# Lightpack5_5.net
KiCad netlist of a schematic drawn in EAGLE
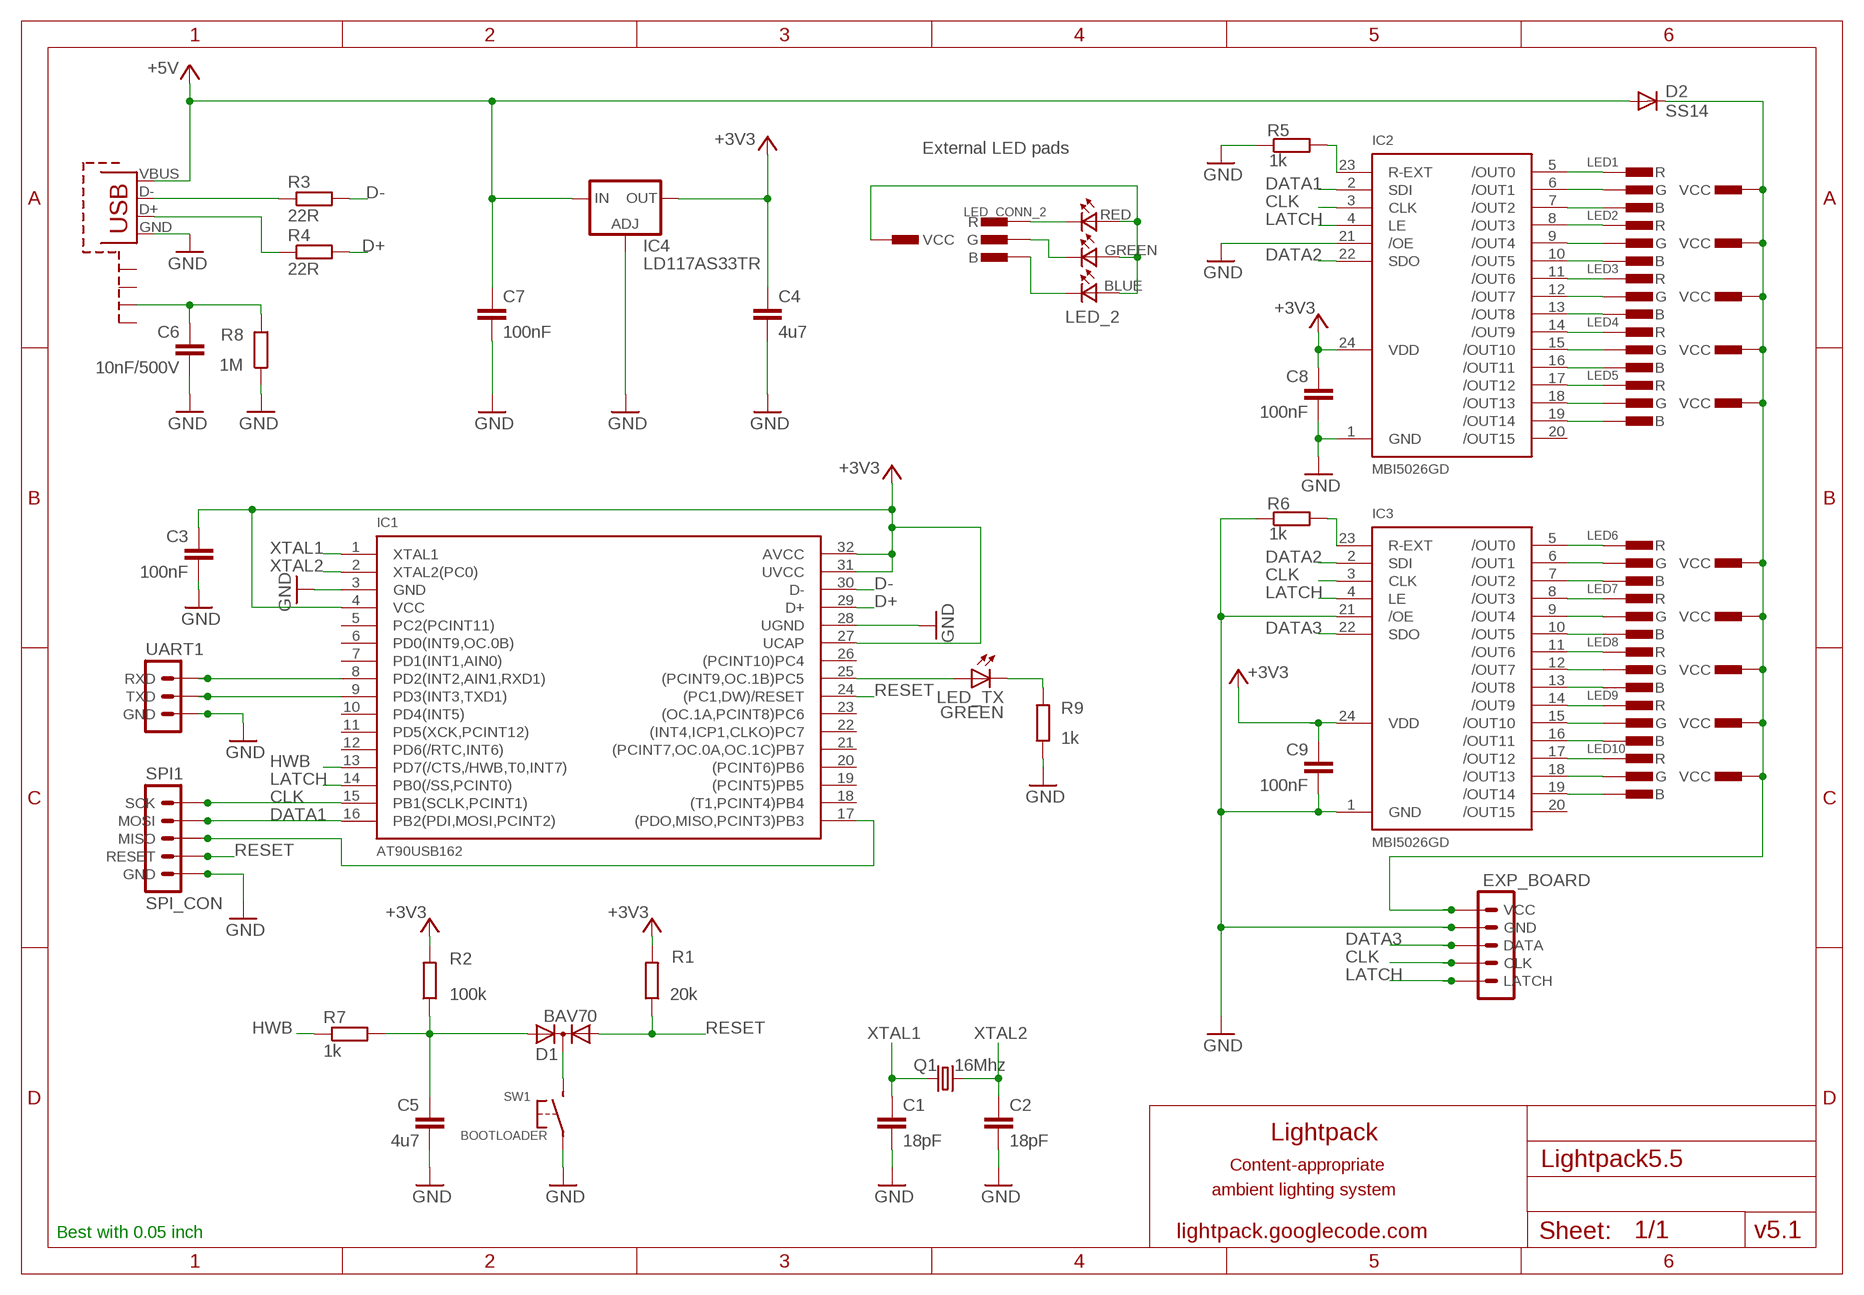
[diagram p0: schematic, sheet 1]

(export (version "E")
  (design (tool "Eeschema 10.0.6"))
  (components
    (comp (ref "C1")
      (value "18pF")
      (footprint "eagle-import:C1206")
      (libsource (lib "eagle-import") (part "C-EUC1206"))
    )
    (comp (ref "C2")
      (value "18pF")
      (footprint "eagle-import:C1206")
      (libsource (lib "eagle-import") (part "C-EUC1206"))
    )
    (comp (ref "C3")
      (value "100nF")
      (footprint "eagle-import:C1206")
      (libsource (lib "eagle-import") (part "C-EUC1206"))
    )
    (comp (ref "C4")
      (value "4u7")
      (footprint "eagle-import:C1206")
      (libsource (lib "eagle-import") (part "C-EUC1206"))
    )
    (comp (ref "C5")
      (value "4u7")
      (footprint "eagle-import:C1206")
      (libsource (lib "eagle-import") (part "C-EUC1206"))
    )
    (comp (ref "C6")
      (value "10nF/500V")
      (footprint "eagle-import:C1206")
      (libsource (lib "eagle-import") (part "C-EUC1206"))
    )
    (comp (ref "C7")
      (value "100nF")
      (footprint "eagle-import:C1206")
      (libsource (lib "eagle-import") (part "C-EUC1206"))
    )
    (comp (ref "C8")
      (value "100nF")
      (footprint "eagle-import:C1206")
      (libsource (lib "eagle-import") (part "C-EUC1206"))
    )
    (comp (ref "C9")
      (value "100nF")
      (footprint "eagle-import:C1206")
      (libsource (lib "eagle-import") (part "C-EUC1206"))
    )
    (comp (ref "D1")
      (value "BAV70")
      (footprint "eagle-import:SOT23")
      (libsource (lib "eagle-import") (part "DIODE-2AC|CASOT23"))
    )
    (comp (ref "D2")
      (value "SS14")
      (footprint "eagle-import:SMB")
      (libsource (lib "eagle-import") (part "DIODE-SMB"))
    )
    (comp (ref "EXP_BOARD")
      (value "MA05-1")
      (footprint "eagle-import:MA05-1")
      (libsource (lib "eagle-import") (part "MA05-1"))
    )
    (comp (ref "IC1")
      (value "AT90USB162")
      (footprint "eagle-import:TQFP32")
      (libsource (lib "eagle-import") (part "AT90USB162"))
    )
    (comp (ref "IC2")
      (value "MBI5026GD")
      (footprint "eagle-import:SOP24-300-1.27")
      (libsource (lib "eagle-import") (part "MBI5026GD"))
    )
    (comp (ref "IC3")
      (value "MBI5026GD")
      (footprint "eagle-import:SOP24-300-1.27")
      (libsource (lib "eagle-import") (part "MBI5026GD"))
    )
    (comp (ref "IC4")
      (value "LD117AS33TR")
      (footprint "eagle-import:SOT223")
      (libsource (lib "eagle-import") (part "LD117A?S33TR"))
    )
    (comp (ref "LED1")
      (value "CON-RGB-LED")
      (footprint "eagle-import:CON-RGB-LED-TH")
      (libsource (lib "eagle-import") (part "CON-RGB-LED-TH"))
    )
    (comp (ref "LED2")
      (value "CON-RGB-LED")
      (footprint "eagle-import:CON-RGB-LED-TH")
      (libsource (lib "eagle-import") (part "CON-RGB-LED-TH"))
    )
    (comp (ref "LED3")
      (value "CON-RGB-LED")
      (footprint "eagle-import:CON-RGB-LED-TH")
      (libsource (lib "eagle-import") (part "CON-RGB-LED-TH"))
    )
    (comp (ref "LED4")
      (value "CON-RGB-LED")
      (footprint "eagle-import:CON-RGB-LED-TH")
      (libsource (lib "eagle-import") (part "CON-RGB-LED-TH"))
    )
    (comp (ref "LED5")
      (value "CON-RGB-LED")
      (footprint "eagle-import:CON-RGB-LED-TH")
      (libsource (lib "eagle-import") (part "CON-RGB-LED-TH"))
    )
    (comp (ref "LED6")
      (value "CON-RGB-LED")
      (footprint "eagle-import:CON-RGB-LED-TH")
      (libsource (lib "eagle-import") (part "CON-RGB-LED-TH"))
    )
    (comp (ref "LED7")
      (value "CON-RGB-LED")
      (footprint "eagle-import:CON-RGB-LED-TH")
      (libsource (lib "eagle-import") (part "CON-RGB-LED-TH"))
    )
    (comp (ref "LED8")
      (value "CON-RGB-LED")
      (footprint "eagle-import:CON-RGB-LED-TH")
      (libsource (lib "eagle-import") (part "CON-RGB-LED-TH"))
    )
    (comp (ref "LED9")
      (value "CON-RGB-LED")
      (footprint "eagle-import:CON-RGB-LED-TH")
      (libsource (lib "eagle-import") (part "CON-RGB-LED-TH"))
    )
    (comp (ref "LED10")
      (value "CON-RGB-LED")
      (footprint "eagle-import:CON-RGB-LED-TH")
      (libsource (lib "eagle-import") (part "CON-RGB-LED-TH"))
    )
    (comp (ref "LED_2")
      (value "TOPLED-3RF-W2SA50TS")
      (footprint "eagle-import:LP2C63-ST-RGB-SR0")
      (libsource (lib "eagle-import") (part "TOPLED-3RF-W2SA50TS"))
    )
    (comp (ref "LED_CONN_2")
      (value "CON-RGB-LED")
      (footprint "eagle-import:CON-RGB-LED-TH-EXT")
      (libsource (lib "eagle-import") (part "CON-RGB-LED-EXT"))
    )
    (comp (ref "LED_TX")
      (value "GREEN")
      (footprint "eagle-import:CHIPLED_0805")
      (libsource (lib "eagle-import") (part "LEDCHIPLED_0805"))
    )
    (comp (ref "Q1")
      (value "16Mhz")
      (footprint "eagle-import:HC49UP")
      (libsource (lib "eagle-import") (part "CRYSTALHC49UP"))
    )
    (comp (ref "R1")
      (value "20k")
      (footprint "eagle-import:R1206")
      (libsource (lib "eagle-import") (part "R-EU_R1206"))
    )
    (comp (ref "R2")
      (value "100k")
      (footprint "eagle-import:R1206")
      (libsource (lib "eagle-import") (part "R-EU_R1206_2"))
    )
    (comp (ref "R3")
      (value "22R")
      (footprint "eagle-import:R1206")
      (libsource (lib "eagle-import") (part "rcl_R-EU_R1206"))
    )
    (comp (ref "R4")
      (value "22R")
      (footprint "eagle-import:R1206")
      (libsource (lib "eagle-import") (part "rcl_R-EU_R1206"))
    )
    (comp (ref "R5")
      (value "1k")
      (footprint "eagle-import:R1206")
      (libsource (lib "eagle-import") (part "R-EU_R1206"))
    )
    (comp (ref "R6")
      (value "1k")
      (footprint "eagle-import:R1206")
      (libsource (lib "eagle-import") (part "R-EU_R1206"))
    )
    (comp (ref "R7")
      (value "1k")
      (footprint "eagle-import:R1206")
      (libsource (lib "eagle-import") (part "rcl_R-EU_R1206"))
    )
    (comp (ref "R8")
      (value "1M")
      (footprint "eagle-import:R1206")
      (libsource (lib "eagle-import") (part "rcl_R-EU_R1206"))
    )
    (comp (ref "R9")
      (value "1k")
      (footprint "eagle-import:R1206")
      (libsource (lib "eagle-import") (part "rcl_R-EU_R1206"))
    )
    (comp (ref "SPI1")
      (value "SPI_CON")
      (footprint "eagle-import:NXT_BRD")
      (libsource (lib "eagle-import") (part "SPI_CON"))
    )
    (comp (ref "SW1")
      (value "BOOTLOADER")
      (footprint "eagle-import:BUTTON-SMD")
      (libsource (lib "eagle-import") (part "BUTTON"))
    )
    (comp (ref "UART1")
      (value "UART3")
      (footprint "eagle-import:UART3")
      (libsource (lib "eagle-import") (part "UART3"))
    )
    (comp (ref "X1")
      (value "USB-MB-S")
      (footprint "eagle-import:USB-MB-S")
      (libsource (lib "eagle-import") (part "USB-MB-S"))
    )
  )
  (nets
    (net (code "1") (name "+3V3") (class "Default")
      (node (ref "C3") (pin "1") (pinfunction "1_1") (pintype "passive"))
      (node (ref "C4") (pin "1") (pinfunction "1_1") (pintype "passive"))
      (node (ref "C8") (pin "1") (pinfunction "1_1") (pintype "passive"))
      (node (ref "C9") (pin "1") (pinfunction "1_1") (pintype "passive"))
      (node (ref "IC1") (pin "27") (pinfunction "UCAP_27") (pintype "bidirectional"))
      (node (ref "IC1") (pin "31") (pinfunction "UVCC_31") (pintype "bidirectional"))
      (node (ref "IC1") (pin "32") (pinfunction "AVCC_32") (pintype "bidirectional"))
      (node (ref "IC1") (pin "4") (pinfunction "VCC_4") (pintype "bidirectional"))
      (node (ref "IC2") (pin "24") (pinfunction "VDD_24") (pintype "bidirectional"))
      (node (ref "IC3") (pin "24") (pinfunction "VDD_24") (pintype "bidirectional"))
      (node (ref "IC4") (pin "4") (pinfunction "OUT_4") (pintype "passive"))
      (node (ref "R1") (pin "2") (pinfunction "2_2") (pintype "passive"))
      (node (ref "R2") (pin "1") (pinfunction "2_1") (pintype "passive"))
    )
    (net (code "2") (name "+5V") (class "Default")
      (node (ref "C7") (pin "1") (pinfunction "1_1") (pintype "passive"))
      (node (ref "D2") (pin "A") (pinfunction "A_A") (pintype "passive"))
      (node (ref "IC4") (pin "3") (pinfunction "IN_3") (pintype "input"))
      (node (ref "X1") (pin "VBUS") (pinfunction "VBUS_VBUS") (pintype "bidirectional"))
    )
    (net (code "3") (name "/CLK") (class "Default")
      (node (ref "EXP_BOARD") (pin "2") (pinfunction "CLK_2") (pintype "passive"))
      (node (ref "IC1") (pin "15") (pinfunction "PB1(SCLK,PCINT1)_15") (pintype "bidirectional"))
      (node (ref "IC2") (pin "3") (pinfunction "CLK_3") (pintype "bidirectional"))
      (node (ref "IC3") (pin "3") (pinfunction "CLK_3") (pintype "bidirectional"))
      (node (ref "SPI1") (pin "2") (pinfunction "SCK_2") (pintype "passive"))
    )
    (net (code "4") (name "/D+") (class "Default")
      (node (ref "IC1") (pin "29") (pinfunction "D+_29") (pintype "bidirectional"))
      (node (ref "R4") (pin "2") (pinfunction "2_2") (pintype "passive"))
    )
    (net (code "5") (name "/D-") (class "Default")
      (node (ref "IC1") (pin "30") (pinfunction "D-_30") (pintype "bidirectional"))
      (node (ref "R3") (pin "2") (pinfunction "2_2") (pintype "passive"))
    )
    (net (code "6") (name "/DATA1") (class "Default")
      (node (ref "IC1") (pin "16") (pinfunction "PB2(PDI,MOSI,PCINT2)_16") (pintype "bidirectional"))
      (node (ref "IC2") (pin "2") (pinfunction "SDI_2") (pintype "bidirectional"))
      (node (ref "SPI1") (pin "3") (pinfunction "MOSI_3") (pintype "passive"))
    )
    (net (code "7") (name "/DATA2") (class "Default")
      (node (ref "IC2") (pin "22") (pinfunction "SDO_22") (pintype "bidirectional"))
      (node (ref "IC3") (pin "2") (pinfunction "SDI_2") (pintype "bidirectional"))
    )
    (net (code "8") (name "/DATA3") (class "Default")
      (node (ref "EXP_BOARD") (pin "3") (pinfunction "DATA_3") (pintype "passive"))
      (node (ref "IC3") (pin "22") (pinfunction "SDO_22") (pintype "bidirectional"))
    )
    (net (code "9") (name "/HWB") (class "Default")
      (node (ref "IC1") (pin "13") (pinfunction "PD7(/CTS,/HWB,T0,INT7)_13") (pintype "bidirectional"))
      (node (ref "R7") (pin "1") (pinfunction "1_1") (pintype "passive"))
    )
    (net (code "10") (name "/LATCH") (class "Default")
      (node (ref "EXP_BOARD") (pin "1") (pinfunction "LATCH_1") (pintype "passive"))
      (node (ref "IC1") (pin "14") (pinfunction "PB0(/SS,PCINT0)_14") (pintype "bidirectional"))
      (node (ref "IC2") (pin "4") (pinfunction "LE_4") (pintype "bidirectional"))
      (node (ref "IC3") (pin "4") (pinfunction "LE_4") (pintype "bidirectional"))
    )
    (net (code "11") (name "/RESET") (class "Default")
      (node (ref "D1") (pin "1") (pinfunction "A1_1") (pintype "passive"))
      (node (ref "IC1") (pin "24") (pinfunction "(PC1,DW)/RESET_24") (pintype "bidirectional"))
      (node (ref "R1") (pin "1") (pinfunction "1_1") (pintype "passive"))
      (node (ref "SPI1") (pin "5-R") (pinfunction "RESET_5-R") (pintype "passive"))
    )
    (net (code "12") (name "/XTAL1") (class "Default")
      (node (ref "C1") (pin "1") (pinfunction "1_1") (pintype "passive"))
      (node (ref "IC1") (pin "1") (pinfunction "XTAL1_1") (pintype "bidirectional"))
      (node (ref "Q1") (pin "1") (pinfunction "1_1") (pintype "passive"))
    )
    (net (code "13") (name "/XTAL2") (class "Default")
      (node (ref "C2") (pin "1") (pinfunction "1_1") (pintype "passive"))
      (node (ref "IC1") (pin "2") (pinfunction "XTAL2(PC0)_2") (pintype "bidirectional"))
      (node (ref "Q1") (pin "2") (pinfunction "2_2") (pintype "passive"))
    )
    (net (code "14") (name "GND") (class "Default")
      (node (ref "C1") (pin "2") (pinfunction "2_2") (pintype "passive"))
      (node (ref "C2") (pin "2") (pinfunction "2_2") (pintype "passive"))
      (node (ref "C3") (pin "2") (pinfunction "2_2") (pintype "passive"))
      (node (ref "C4") (pin "2") (pinfunction "2_2") (pintype "passive"))
      (node (ref "C5") (pin "2") (pinfunction "2_2") (pintype "passive"))
      (node (ref "C6") (pin "2") (pinfunction "2_2") (pintype "passive"))
      (node (ref "C7") (pin "2") (pinfunction "2_2") (pintype "passive"))
      (node (ref "C8") (pin "2") (pinfunction "2_2") (pintype "passive"))
      (node (ref "C9") (pin "2") (pinfunction "2_2") (pintype "passive"))
      (node (ref "EXP_BOARD") (pin "4") (pinfunction "GND_4") (pintype "passive"))
      (node (ref "IC1") (pin "28") (pinfunction "UGND_28") (pintype "bidirectional"))
      (node (ref "IC1") (pin "3") (pinfunction "GND_3") (pintype "bidirectional"))
      (node (ref "IC2") (pin "1") (pinfunction "GND_1") (pintype "bidirectional"))
      (node (ref "IC2") (pin "21") (pinfunction "/OE_21") (pintype "bidirectional"))
      (node (ref "IC3") (pin "1") (pinfunction "GND_1") (pintype "bidirectional"))
      (node (ref "IC3") (pin "21") (pinfunction "/OE_21") (pintype "bidirectional"))
      (node (ref "IC4") (pin "1") (pinfunction "ADJ_1") (pintype "input"))
      (node (ref "R5") (pin "1") (pinfunction "1_1") (pintype "passive"))
      (node (ref "R6") (pin "1") (pinfunction "1_1") (pintype "passive"))
      (node (ref "R8") (pin "1") (pinfunction "1_1") (pintype "passive"))
      (node (ref "R9") (pin "1") (pinfunction "1_1") (pintype "passive"))
      (node (ref "SPI1") (pin "1-L") (pinfunction "GND_1-L") (pintype "passive"))
      (node (ref "SW1") (pin "1") (pinfunction "1_1") (pintype "passive"))
      (node (ref "UART1") (pin "1-L") (pinfunction "GND_1-L") (pintype "passive"))
      (node (ref "X1") (pin "GND") (pinfunction "GND_GND") (pintype "bidirectional"))
    )
    (net (code "15") (name "Net-(C6-Pad1)") (class "Default")
      (node (ref "C6") (pin "1") (pinfunction "1_1") (pintype "passive"))
      (node (ref "R8") (pin "2") (pinfunction "2_2") (pintype "passive"))
      (node (ref "X1") (pin "SHIELD3") (pinfunction "SHIELD3_SHIELD3") (pintype "bidirectional"))
    )
    (net (code "16") (name "Net-(D1-A2)") (class "Default")
      (node (ref "C5") (pin "1") (pinfunction "1_1") (pintype "passive"))
      (node (ref "D1") (pin "2") (pinfunction "A2_2") (pintype "passive"))
      (node (ref "R2") (pin "2") (pinfunction "1_2") (pintype "passive"))
      (node (ref "R7") (pin "2") (pinfunction "2_2") (pintype "passive"))
    )
    (net (code "17") (name "Net-(D1-C)") (class "Default")
      (node (ref "D1") (pin "3") (pinfunction "C_3") (pintype "passive"))
      (node (ref "SW1") (pin "2") (pinfunction "2_2") (pintype "passive"))
    )
    (net (code "18") (name "Net-(EXP_BOARD-VCC)") (class "Default")
      (node (ref "D2") (pin "C") (pinfunction "C_C") (pintype "passive"))
      (node (ref "EXP_BOARD") (pin "5") (pinfunction "VCC_5") (pintype "passive"))
      (node (ref "LED1") (pin "4.VCC") (pinfunction "VCC_4.VCC") (pintype "bidirectional"))
      (node (ref "LED10") (pin "4.VCC") (pinfunction "VCC_4.VCC") (pintype "bidirectional"))
      (node (ref "LED2") (pin "4.VCC") (pinfunction "VCC_4.VCC") (pintype "bidirectional"))
      (node (ref "LED3") (pin "4.VCC") (pinfunction "VCC_4.VCC") (pintype "bidirectional"))
      (node (ref "LED4") (pin "4.VCC") (pinfunction "VCC_4.VCC") (pintype "bidirectional"))
      (node (ref "LED5") (pin "4.VCC") (pinfunction "VCC_4.VCC") (pintype "bidirectional"))
      (node (ref "LED6") (pin "4.VCC") (pinfunction "VCC_4.VCC") (pintype "bidirectional"))
      (node (ref "LED7") (pin "4.VCC") (pinfunction "VCC_4.VCC") (pintype "bidirectional"))
      (node (ref "LED8") (pin "4.VCC") (pinfunction "VCC_4.VCC") (pintype "bidirectional"))
      (node (ref "LED9") (pin "4.VCC") (pinfunction "VCC_4.VCC") (pintype "bidirectional"))
    )
    (net (code "19") (name "Net-(IC1-(PCINT9,OC.1B)PC5)") (class "Default")
      (node (ref "IC1") (pin "25") (pinfunction "(PCINT9,OC.1B)PC5_25") (pintype "bidirectional"))
      (node (ref "LED_TX") (pin "A") (pinfunction "A_A") (pintype "passive"))
    )
    (net (code "20") (name "Net-(IC1-(PDO,MISO,PCINT3)PB3)") (class "Default")
      (node (ref "IC1") (pin "17") (pinfunction "(PDO,MISO,PCINT3)PB3_17") (pintype "bidirectional"))
      (node (ref "SPI1") (pin "4") (pinfunction "MISO_4") (pintype "passive"))
    )
    (net (code "21") (name "Net-(IC1-PD2(INT2,AIN1,RXD1))") (class "Default")
      (node (ref "IC1") (pin "8") (pinfunction "PD2(INT2,AIN1,RXD1)_8") (pintype "bidirectional"))
      (node (ref "UART1") (pin "2") (pinfunction "RXD_2") (pintype "passive"))
    )
    (net (code "22") (name "Net-(IC1-PD3(INT3,TXD1))") (class "Default")
      (node (ref "IC1") (pin "9") (pinfunction "PD3(INT3,TXD1)_9") (pintype "bidirectional"))
      (node (ref "UART1") (pin "3-R") (pinfunction "TXD_3-R") (pintype "passive"))
    )
    (net (code "23") (name "Net-(IC2-R-EXT)") (class "Default")
      (node (ref "IC2") (pin "23") (pinfunction "R-EXT_23") (pintype "bidirectional"))
      (node (ref "R5") (pin "2") (pinfunction "2_2") (pintype "passive"))
    )
    (net (code "24") (name "Net-(IC2-{slash}OUT0)") (class "Default")
      (node (ref "IC2") (pin "5") (pinfunction "/OUT0_5") (pintype "bidirectional"))
      (node (ref "LED1") (pin "3.R") (pinfunction "R_3.R") (pintype "bidirectional"))
    )
    (net (code "25") (name "Net-(IC2-{slash}OUT1)") (class "Default")
      (node (ref "IC2") (pin "6") (pinfunction "/OUT1_6") (pintype "bidirectional"))
      (node (ref "LED1") (pin "2.G") (pinfunction "G_2.G") (pintype "bidirectional"))
    )
    (net (code "26") (name "Net-(IC2-{slash}OUT2)") (class "Default")
      (node (ref "IC2") (pin "7") (pinfunction "/OUT2_7") (pintype "bidirectional"))
      (node (ref "LED1") (pin "1.B") (pinfunction "B_1.B") (pintype "bidirectional"))
    )
    (net (code "27") (name "Net-(IC2-{slash}OUT3)") (class "Default")
      (node (ref "IC2") (pin "8") (pinfunction "/OUT3_8") (pintype "bidirectional"))
      (node (ref "LED2") (pin "3.R") (pinfunction "R_3.R") (pintype "bidirectional"))
    )
    (net (code "28") (name "Net-(IC2-{slash}OUT4)") (class "Default")
      (node (ref "IC2") (pin "9") (pinfunction "/OUT4_9") (pintype "bidirectional"))
      (node (ref "LED2") (pin "2.G") (pinfunction "G_2.G") (pintype "bidirectional"))
    )
    (net (code "29") (name "Net-(IC2-{slash}OUT5)") (class "Default")
      (node (ref "IC2") (pin "10") (pinfunction "/OUT5_10") (pintype "bidirectional"))
      (node (ref "LED2") (pin "1.B") (pinfunction "B_1.B") (pintype "bidirectional"))
    )
    (net (code "30") (name "Net-(IC2-{slash}OUT6)") (class "Default")
      (node (ref "IC2") (pin "11") (pinfunction "/OUT6_11") (pintype "bidirectional"))
      (node (ref "LED3") (pin "3.R") (pinfunction "R_3.R") (pintype "bidirectional"))
    )
    (net (code "31") (name "Net-(IC2-{slash}OUT7)") (class "Default")
      (node (ref "IC2") (pin "12") (pinfunction "/OUT7_12") (pintype "bidirectional"))
      (node (ref "LED3") (pin "2.G") (pinfunction "G_2.G") (pintype "bidirectional"))
    )
    (net (code "32") (name "Net-(IC2-{slash}OUT8)") (class "Default")
      (node (ref "IC2") (pin "13") (pinfunction "/OUT8_13") (pintype "bidirectional"))
      (node (ref "LED3") (pin "1.B") (pinfunction "B_1.B") (pintype "bidirectional"))
    )
    (net (code "33") (name "Net-(IC2-{slash}OUT9)") (class "Default")
      (node (ref "IC2") (pin "14") (pinfunction "/OUT9_14") (pintype "bidirectional"))
      (node (ref "LED4") (pin "3.R") (pinfunction "R_3.R") (pintype "bidirectional"))
    )
    (net (code "34") (name "Net-(IC2-{slash}OUT10)") (class "Default")
      (node (ref "IC2") (pin "15") (pinfunction "/OUT10_15") (pintype "bidirectional"))
      (node (ref "LED4") (pin "2.G") (pinfunction "G_2.G") (pintype "bidirectional"))
    )
    (net (code "35") (name "Net-(IC2-{slash}OUT11)") (class "Default")
      (node (ref "IC2") (pin "16") (pinfunction "/OUT11_16") (pintype "bidirectional"))
      (node (ref "LED4") (pin "1.B") (pinfunction "B_1.B") (pintype "bidirectional"))
    )
    (net (code "36") (name "Net-(IC2-{slash}OUT12)") (class "Default")
      (node (ref "IC2") (pin "17") (pinfunction "/OUT12_17") (pintype "bidirectional"))
      (node (ref "LED5") (pin "3.R") (pinfunction "R_3.R") (pintype "bidirectional"))
    )
    (net (code "37") (name "Net-(IC2-{slash}OUT13)") (class "Default")
      (node (ref "IC2") (pin "18") (pinfunction "/OUT13_18") (pintype "bidirectional"))
      (node (ref "LED5") (pin "2.G") (pinfunction "G_2.G") (pintype "bidirectional"))
    )
    (net (code "38") (name "Net-(IC2-{slash}OUT14)") (class "Default")
      (node (ref "IC2") (pin "19") (pinfunction "/OUT14_19") (pintype "bidirectional"))
      (node (ref "LED5") (pin "1.B") (pinfunction "B_1.B") (pintype "bidirectional"))
    )
    (net (code "39") (name "Net-(IC3-R-EXT)") (class "Default")
      (node (ref "IC3") (pin "23") (pinfunction "R-EXT_23") (pintype "bidirectional"))
      (node (ref "R6") (pin "2") (pinfunction "2_2") (pintype "passive"))
    )
    (net (code "40") (name "Net-(IC3-{slash}OUT0)") (class "Default")
      (node (ref "IC3") (pin "5") (pinfunction "/OUT0_5") (pintype "bidirectional"))
      (node (ref "LED6") (pin "3.R") (pinfunction "R_3.R") (pintype "bidirectional"))
    )
    (net (code "41") (name "Net-(IC3-{slash}OUT1)") (class "Default")
      (node (ref "IC3") (pin "6") (pinfunction "/OUT1_6") (pintype "bidirectional"))
      (node (ref "LED6") (pin "2.G") (pinfunction "G_2.G") (pintype "bidirectional"))
    )
    (net (code "42") (name "Net-(IC3-{slash}OUT2)") (class "Default")
      (node (ref "IC3") (pin "7") (pinfunction "/OUT2_7") (pintype "bidirectional"))
      (node (ref "LED6") (pin "1.B") (pinfunction "B_1.B") (pintype "bidirectional"))
    )
    (net (code "43") (name "Net-(IC3-{slash}OUT3)") (class "Default")
      (node (ref "IC3") (pin "8") (pinfunction "/OUT3_8") (pintype "bidirectional"))
      (node (ref "LED7") (pin "3.R") (pinfunction "R_3.R") (pintype "bidirectional"))
    )
    (net (code "44") (name "Net-(IC3-{slash}OUT4)") (class "Default")
      (node (ref "IC3") (pin "9") (pinfunction "/OUT4_9") (pintype "bidirectional"))
      (node (ref "LED7") (pin "2.G") (pinfunction "G_2.G") (pintype "bidirectional"))
    )
    (net (code "45") (name "Net-(IC3-{slash}OUT5)") (class "Default")
      (node (ref "IC3") (pin "10") (pinfunction "/OUT5_10") (pintype "bidirectional"))
      (node (ref "LED7") (pin "1.B") (pinfunction "B_1.B") (pintype "bidirectional"))
    )
    (net (code "46") (name "Net-(IC3-{slash}OUT6)") (class "Default")
      (node (ref "IC3") (pin "11") (pinfunction "/OUT6_11") (pintype "bidirectional"))
      (node (ref "LED8") (pin "3.R") (pinfunction "R_3.R") (pintype "bidirectional"))
    )
    (net (code "47") (name "Net-(IC3-{slash}OUT7)") (class "Default")
      (node (ref "IC3") (pin "12") (pinfunction "/OUT7_12") (pintype "bidirectional"))
      (node (ref "LED8") (pin "2.G") (pinfunction "G_2.G") (pintype "bidirectional"))
    )
    (net (code "48") (name "Net-(IC3-{slash}OUT8)") (class "Default")
      (node (ref "IC3") (pin "13") (pinfunction "/OUT8_13") (pintype "bidirectional"))
      (node (ref "LED8") (pin "1.B") (pinfunction "B_1.B") (pintype "bidirectional"))
    )
    (net (code "49") (name "Net-(IC3-{slash}OUT9)") (class "Default")
      (node (ref "IC3") (pin "14") (pinfunction "/OUT9_14") (pintype "bidirectional"))
      (node (ref "LED9") (pin "3.R") (pinfunction "R_3.R") (pintype "bidirectional"))
    )
    (net (code "50") (name "Net-(IC3-{slash}OUT10)") (class "Default")
      (node (ref "IC3") (pin "15") (pinfunction "/OUT10_15") (pintype "bidirectional"))
      (node (ref "LED9") (pin "2.G") (pinfunction "G_2.G") (pintype "bidirectional"))
    )
    (net (code "51") (name "Net-(IC3-{slash}OUT11)") (class "Default")
      (node (ref "IC3") (pin "16") (pinfunction "/OUT11_16") (pintype "bidirectional"))
      (node (ref "LED9") (pin "1.B") (pinfunction "B_1.B") (pintype "bidirectional"))
    )
    (net (code "52") (name "Net-(IC3-{slash}OUT12)") (class "Default")
      (node (ref "IC3") (pin "17") (pinfunction "/OUT12_17") (pintype "bidirectional"))
      (node (ref "LED10") (pin "3.R") (pinfunction "R_3.R") (pintype "bidirectional"))
    )
    (net (code "53") (name "Net-(IC3-{slash}OUT13)") (class "Default")
      (node (ref "IC3") (pin "18") (pinfunction "/OUT13_18") (pintype "bidirectional"))
      (node (ref "LED10") (pin "2.G") (pinfunction "G_2.G") (pintype "bidirectional"))
    )
    (net (code "54") (name "Net-(IC3-{slash}OUT14)") (class "Default")
      (node (ref "IC3") (pin "19") (pinfunction "/OUT14_19") (pintype "bidirectional"))
      (node (ref "LED10") (pin "1.B") (pinfunction "B_1.B") (pintype "bidirectional"))
    )
    (net (code "55") (name "Net-(LED_CONN_2-B)") (class "Default")
      (node (ref "LED_2") (pin "CBLUE") (pinfunction "CBLUE_CBLUE") (pintype "passive"))
      (node (ref "LED_CONN_2") (pin "1.B") (pinfunction "B_1.B") (pintype "bidirectional"))
    )
    (net (code "56") (name "Net-(LED_CONN_2-G)") (class "Default")
      (node (ref "LED_2") (pin "CGREEN") (pinfunction "CGREEN_CGREEN") (pintype "passive"))
      (node (ref "LED_CONN_2") (pin "2.G") (pinfunction "G_2.G") (pintype "bidirectional"))
    )
    (net (code "57") (name "Net-(LED_CONN_2-R)") (class "Default")
      (node (ref "LED_2") (pin "CRED") (pinfunction "CRED_CRED") (pintype "passive"))
      (node (ref "LED_CONN_2") (pin "3.R") (pinfunction "R_3.R") (pintype "bidirectional"))
    )
    (net (code "58") (name "Net-(LED_CONN_2-VCC)") (class "Default")
      (node (ref "LED_2") (pin "BLUE") (pinfunction "BLUE_BLUE") (pintype "passive"))
      (node (ref "LED_2") (pin "GREEN") (pinfunction "GREEN_GREEN") (pintype "passive"))
      (node (ref "LED_2") (pin "RED") (pinfunction "RED_RED") (pintype "passive"))
      (node (ref "LED_CONN_2") (pin "4.VCC") (pinfunction "VCC_4.VCC") (pintype "bidirectional"))
    )
    (net (code "59") (name "Net-(LED_TX-PadC)") (class "Default")
      (node (ref "LED_TX") (pin "C") (pinfunction "C_C") (pintype "passive"))
      (node (ref "R9") (pin "2") (pinfunction "2_2") (pintype "passive"))
    )
    (net (code "60") (name "Net-(R3-Pad1)") (class "Default")
      (node (ref "R3") (pin "1") (pinfunction "1_1") (pintype "passive"))
      (node (ref "X1") (pin "D-") (pinfunction "D-_D-") (pintype "bidirectional"))
    )
    (net (code "61") (name "Net-(R4-Pad1)") (class "Default")
      (node (ref "R4") (pin "1") (pinfunction "1_1") (pintype "passive"))
      (node (ref "X1") (pin "D+") (pinfunction "D+_D+") (pintype "bidirectional"))
    )
    (net (code "62") (name "unconnected-(IC1-(INT4,ICP1,CLKO)PC7-Pad22)") (class "Default")
      (node (ref "IC1") (pin "22") (pinfunction "(INT4,ICP1,CLKO)PC7_22") (pintype "bidirectional"))
    )
    (net (code "63") (name "unconnected-(IC1-(OC.1A,PCINT8)PC6-Pad23)") (class "Default")
      (node (ref "IC1") (pin "23") (pinfunction "(OC.1A,PCINT8)PC6_23") (pintype "bidirectional"))
    )
    (net (code "64") (name "unconnected-(IC1-(PCINT5)PB5-Pad19)") (class "Default")
      (node (ref "IC1") (pin "19") (pinfunction "(PCINT5)PB5_19") (pintype "bidirectional"))
    )
    (net (code "65") (name "unconnected-(IC1-(PCINT6)PB6-Pad20)") (class "Default")
      (node (ref "IC1") (pin "20") (pinfunction "(PCINT6)PB6_20") (pintype "bidirectional"))
    )
    (net (code "66") (name "unconnected-(IC1-(PCINT7,OC.0A,OC.1C)PB7-Pad21)") (class "Default")
      (node (ref "IC1") (pin "21") (pinfunction "(PCINT7,OC.0A,OC.1C)PB7_21") (pintype "bidirectional"))
    )
    (net (code "67") (name "unconnected-(IC1-(PCINT10)PC4-Pad26)") (class "Default")
      (node (ref "IC1") (pin "26") (pinfunction "(PCINT10)PC4_26") (pintype "bidirectional"))
    )
    (net (code "68") (name "unconnected-(IC1-(T1,PCINT4)PB4-Pad18)") (class "Default")
      (node (ref "IC1") (pin "18") (pinfunction "(T1,PCINT4)PB4_18") (pintype "bidirectional"))
    )
    (net (code "69") (name "unconnected-(IC1-PC2(PCINT11)-Pad5)") (class "Default")
      (node (ref "IC1") (pin "5") (pinfunction "PC2(PCINT11)_5") (pintype "bidirectional"))
    )
    (net (code "70") (name "unconnected-(IC1-PD0(INT9,OC.0B)-Pad6)") (class "Default")
      (node (ref "IC1") (pin "6") (pinfunction "PD0(INT9,OC.0B)_6") (pintype "bidirectional"))
    )
    (net (code "71") (name "unconnected-(IC1-PD1(INT1,AIN0)-Pad7)") (class "Default")
      (node (ref "IC1") (pin "7") (pinfunction "PD1(INT1,AIN0)_7") (pintype "bidirectional"))
    )
    (net (code "72") (name "unconnected-(IC1-PD4(INT5)-Pad10)") (class "Default")
      (node (ref "IC1") (pin "10") (pinfunction "PD4(INT5)_10") (pintype "bidirectional"))
    )
    (net (code "73") (name "unconnected-(IC1-PD5(XCK,PCINT12)-Pad11)") (class "Default")
      (node (ref "IC1") (pin "11") (pinfunction "PD5(XCK,PCINT12)_11") (pintype "bidirectional"))
    )
    (net (code "74") (name "unconnected-(IC1-PD6({slash}RTC,INT6)-Pad12)") (class "Default")
      (node (ref "IC1") (pin "12") (pinfunction "PD6(/RTC,INT6)_12") (pintype "bidirectional"))
    )
    (net (code "75") (name "unconnected-(IC2-{slash}OUT15-Pad20)") (class "Default")
      (node (ref "IC2") (pin "20") (pinfunction "/OUT15_20") (pintype "bidirectional"))
    )
    (net (code "76") (name "unconnected-(IC3-{slash}OUT15-Pad20)") (class "Default")
      (node (ref "IC3") (pin "20") (pinfunction "/OUT15_20") (pintype "bidirectional"))
    )
    (net (code "77") (name "unconnected-(X1-PadSHIELD1)") (class "Default")
      (node (ref "X1") (pin "SHIELD1") (pinfunction "SHIELD1_SHIELD1") (pintype "bidirectional"))
    )
    (net (code "78") (name "unconnected-(X1-PadSHIELD2)") (class "Default")
      (node (ref "X1") (pin "SHIELD2") (pinfunction "SHIELD2_SHIELD2") (pintype "bidirectional"))
    )
    (net (code "79") (name "unconnected-(X1-PadSHIELD4)") (class "Default")
      (node (ref "X1") (pin "SHIELD4") (pinfunction "SHIELD4_SHIELD4") (pintype "bidirectional"))
    )
  )
)
